# esp32-thing.net
KiCad netlist of a schematic drawn in EAGLE
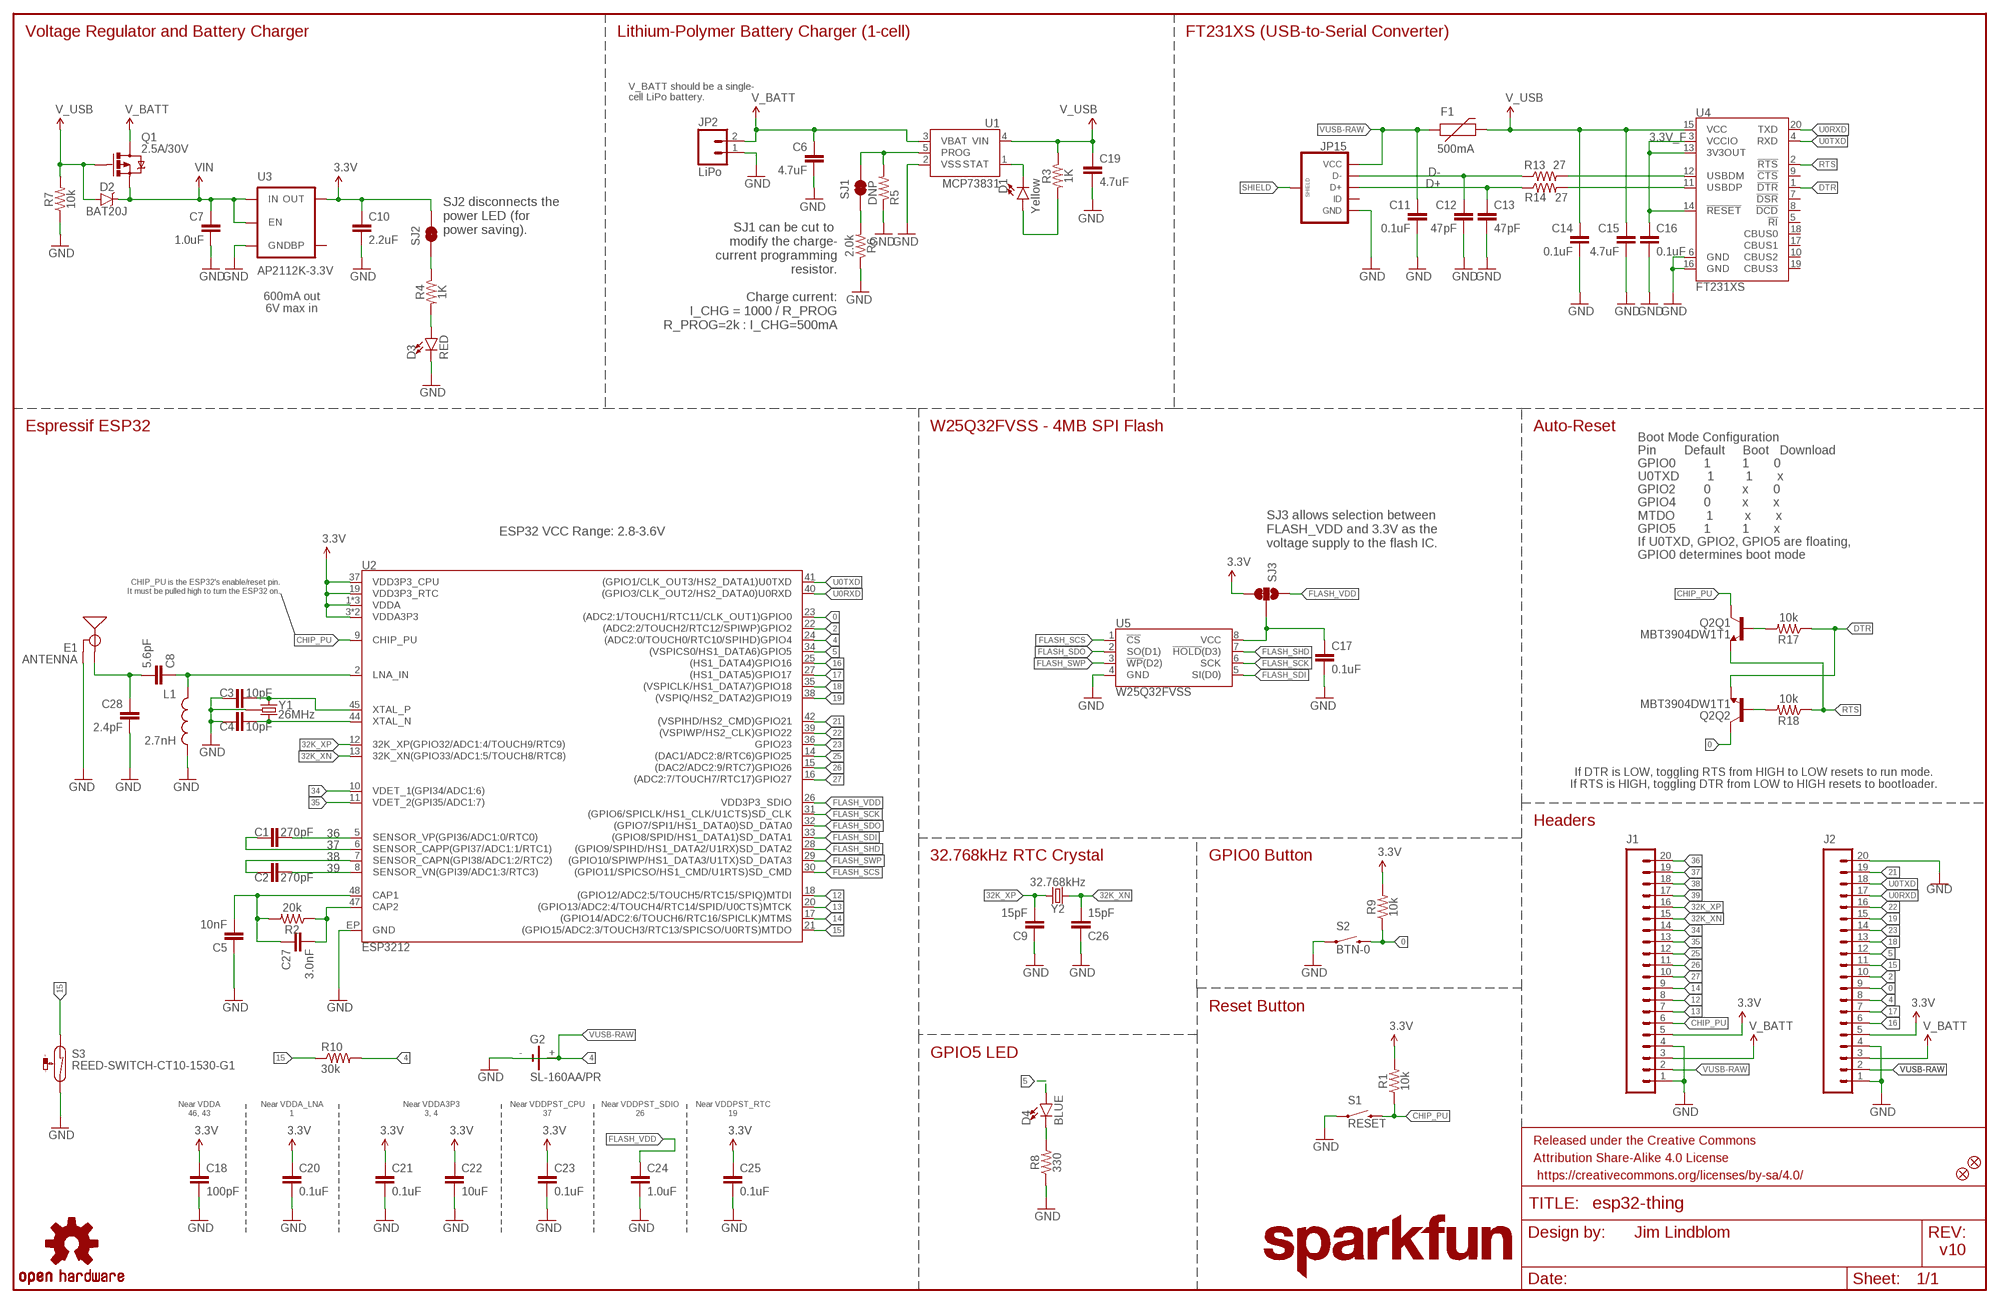
[diagram p0: schematic, sheet 1]

(export (version "E")
  (design (tool "Eeschema 10.0.6"))
  (components
    (comp (ref "C1")
      (value "270pF")
      (footprint "eagle-import:0603")
      (libsource (lib "eagle-import") (part "270PF-50V-5%(0603)"))
    )
    (comp (ref "C2")
      (value "270pF")
      (footprint "eagle-import:0603")
      (libsource (lib "eagle-import") (part "270PF-50V-5%(0603)"))
    )
    (comp (ref "C3")
      (value "10pF")
      (footprint "eagle-import:0603")
      (libsource (lib "eagle-import") (part "10PF-0603-50V-5%"))
    )
    (comp (ref "C4")
      (value "10pF")
      (footprint "eagle-import:0603")
      (libsource (lib "eagle-import") (part "10PF-0603-50V-5%"))
    )
    (comp (ref "C5")
      (value "10nF")
      (footprint "eagle-import:0603")
      (libsource (lib "eagle-import") (part "10NF-0603-50V-10%"))
    )
    (comp (ref "C6")
      (value "4.7uF")
      (footprint "eagle-import:0603")
      (libsource (lib "eagle-import") (part "4.7UF0603"))
    )
    (comp (ref "C7")
      (value "1.0uF")
      (footprint "eagle-import:0805")
      (libsource (lib "eagle-import") (part "1.0UF-0805-25V-(+80/-20%)"))
    )
    (comp (ref "C8")
      (value "5.6pF")
      (footprint "eagle-import:0603")
      (libsource (lib "eagle-import") (part "5.6PF-50V-5%(0603)"))
    )
    (comp (ref "C9")
      (value "15pF")
      (footprint "eagle-import:0603")
      (libsource (lib "eagle-import") (part "15PF-0603-50V-5%"))
    )
    (comp (ref "C10")
      (value "2.2uF")
      (footprint "eagle-import:0603")
      (libsource (lib "eagle-import") (part "2.2UF-0603-10V-20%"))
    )
    (comp (ref "C11")
      (value "0.1uF")
      (footprint "eagle-import:0603")
      (libsource (lib "eagle-import") (part "0.1UF-0603-25V-(+80/-20%)"))
    )
    (comp (ref "C12")
      (value "47pF")
      (footprint "eagle-import:0603")
      (libsource (lib "eagle-import") (part "47PF-0603-50V-5%"))
    )
    (comp (ref "C13")
      (value "47pF")
      (footprint "eagle-import:0603")
      (libsource (lib "eagle-import") (part "47PF-0603-50V-5%"))
    )
    (comp (ref "C14")
      (value "0.1uF")
      (footprint "eagle-import:0603")
      (libsource (lib "eagle-import") (part "0.1UF-0603-25V-(+80/-20%)"))
    )
    (comp (ref "C15")
      (value "4.7uF")
      (footprint "eagle-import:0603-CAP")
      (libsource (lib "eagle-import") (part "4.7UF-6.3V-10%(0603)0603"))
    )
    (comp (ref "C16")
      (value "0.1uF")
      (footprint "eagle-import:0603")
      (libsource (lib "eagle-import") (part "0.1UF-0603-25V-(+80/-20%)"))
    )
    (comp (ref "C17")
      (value "0.1uF")
      (footprint "eagle-import:0603")
      (libsource (lib "eagle-import") (part "0.1UF-0603-25V-(+80/-20%)"))
    )
    (comp (ref "C18")
      (value "100pF")
      (footprint "eagle-import:0603")
      (libsource (lib "eagle-import") (part "100PF-0603-50V-5%"))
    )
    (comp (ref "C19")
      (value "4.7uF")
      (footprint "eagle-import:0603")
      (libsource (lib "eagle-import") (part "4.7UF0603"))
    )
    (comp (ref "C20")
      (value "0.1uF")
      (footprint "eagle-import:0603")
      (libsource (lib "eagle-import") (part "0.1UF-0603-25V-(+80/-20%)"))
    )
    (comp (ref "C21")
      (value "0.1uF")
      (footprint "eagle-import:0603")
      (libsource (lib "eagle-import") (part "0.1UF-0603-25V-(+80/-20%)"))
    )
    (comp (ref "C22")
      (value "10uF")
      (footprint "eagle-import:0603")
      (libsource (lib "eagle-import") (part "10UF-0603-6.3V-20%"))
    )
    (comp (ref "C23")
      (value "0.1uF")
      (footprint "eagle-import:0603")
      (libsource (lib "eagle-import") (part "0.1UF-0603-25V-(+80/-20%)"))
    )
    (comp (ref "C24")
      (value "1.0uF")
      (footprint "eagle-import:0603")
      (libsource (lib "eagle-import") (part "1.0UF-0603-16V-10%"))
    )
    (comp (ref "C25")
      (value "0.1uF")
      (footprint "eagle-import:0603")
      (libsource (lib "eagle-import") (part "0.1UF-0603-25V-(+80/-20%)"))
    )
    (comp (ref "C26")
      (value "15pF")
      (footprint "eagle-import:0603")
      (libsource (lib "eagle-import") (part "15PF-0603-50V-5%"))
    )
    (comp (ref "C27")
      (value "3.0nF")
      (footprint "eagle-import:0603")
      (libsource (lib "eagle-import") (part "3.0NF-0603-50V-5%"))
    )
    (comp (ref "C28")
      (value "2.4pF")
      (footprint "eagle-import:0603")
      (libsource (lib "eagle-import") (part "2.4PF-0603-50V-5%"))
    )
    (comp (ref "D1")
      (value "Yellow")
      (footprint "eagle-import:LED-0603")
      (libsource (lib "eagle-import") (part "LED-YELLOW0603"))
    )
    (comp (ref "D2")
      (value "BAT20J")
      (footprint "eagle-import:SOD-323")
      (libsource (lib "eagle-import") (part "DIODE-SCHOTTKY-BAT20J"))
    )
    (comp (ref "D3")
      (value "RED")
      (footprint "eagle-import:LED-0603")
      (libsource (lib "eagle-import") (part "LED-RED0603"))
    )
    (comp (ref "D4")
      (value "BLUE")
      (footprint "eagle-import:LED-0603")
      (libsource (lib "eagle-import") (part "LED-BLUE0603"))
    )
    (comp (ref "E1")
      (value "ANTENNA")
      (footprint "eagle-import:TRACE_ANTENNA_2.4GHZ_25.7MM_TUNED")
      (libsource (lib "eagle-import") (part "ANTENNATRACE-TUNED"))
    )
    (comp (ref "F1")
      (value "500mA")
      (footprint "eagle-import:PTC-1206")
      (libsource (lib "eagle-import") (part "PTCSMD"))
    )
    (comp (ref "FD1")
      (value "FIDUCIALUFIDUCIAL")
      (footprint "eagle-import:MICRO-FIDUCIAL")
      (libsource (lib "eagle-import") (part "FIDUCIALUFIDUCIAL"))
    )
    (comp (ref "FD2")
      (value "FIDUCIALUFIDUCIAL")
      (footprint "eagle-import:MICRO-FIDUCIAL")
      (libsource (lib "eagle-import") (part "FIDUCIALUFIDUCIAL"))
    )
    (comp (ref "FRAME1")
      (value "FRAME-LEDGER")
      (footprint "eagle-import:CREATIVE_COMMONS")
      (libsource (lib "eagle-import") (part "FRAME-LEDGER"))
    )
    (comp (ref "G2")
      (value "SL-160AA/PR")
      (footprint "eagle-import:SL-160AA_PR")
      (libsource (lib "eagle-import") (part "SL-160AA/PR"))
    )
    (comp (ref "J1")
      (value "M20NOSILK")
      (footprint "eagle-import:1X20_NOSILK")
      (libsource (lib "eagle-import") (part "M20NOSILK"))
    )
    (comp (ref "J2")
      (value "M20NOSILK")
      (footprint "eagle-import:1X20_NOSILK")
      (libsource (lib "eagle-import") (part "M20NOSILK"))
    )
    (comp (ref "JP2")
      (value "LiPo")
      (footprint "eagle-import:JST-2-PTH")
      (libsource (lib "eagle-import") (part "M02JST-PTH-2"))
    )
    (comp (ref "JP15")
      (value "USB_MICROB_PLUGCONN-11752")
      (footprint "eagle-import:USB-B-MICRO-SMD_V03")
      (libsource (lib "eagle-import") (part "USB_MICROB_PLUGCONN-11752"))
    )
    (comp (ref "L1")
      (value "2.7nH")
      (footprint "eagle-import:0603")
      (libsource (lib "eagle-import") (part "INDUCTOR0603"))
    )
    (comp (ref "LOGO1")
      (value "SFE_LOGO_NAME.2_INCH")
      (footprint "eagle-import:SFE_LOGO_NAME_.2")
      (libsource (lib "eagle-import") (part "SFE_LOGO_NAME.2_INCH"))
    )
    (comp (ref "LOGO2")
      (value "OSHW-LOGOMINI")
      (footprint "eagle-import:OSHW-LOGO-MINI")
      (libsource (lib "eagle-import") (part "OSHW-LOGOMINI"))
    )
    (comp (ref "LOGO3")
      (value "SFE_LOGO_NAME.2_INCH")
      (footprint "eagle-import:SFE_LOGO_NAME_.2")
      (libsource (lib "eagle-import") (part "SFE_LOGO_NAME.2_INCH"))
    )
    (comp (ref "Q1")
      (value "2.5A/30V")
      (footprint "eagle-import:SOT23-3")
      (libsource (lib "eagle-import") (part "MOSFET-PCHANNELDMG2307L"))
    )
    (comp (ref "Q2")
      (value "MBT3904DW1T1")
      (footprint "eagle-import:SC70-6")
      (libsource (lib "eagle-import") (part "MBT3904DW1T1"))
    )
    (comp (ref "R1")
      (value "10k")
      (footprint "eagle-import:0603")
      (libsource (lib "eagle-import") (part "10KOHM-1/10W-1%(0603)0603"))
    )
    (comp (ref "R2")
      (value "20k")
      (footprint "eagle-import:0603")
      (libsource (lib "eagle-import") (part "20KOHM-0603-1/10W-1%"))
    )
    (comp (ref "R3")
      (value "1K")
      (footprint "eagle-import:0603")
      (libsource (lib "eagle-import") (part "1KOHM-1/10W-1%(0603)"))
    )
    (comp (ref "R4")
      (value "1K")
      (footprint "eagle-import:0603")
      (libsource (lib "eagle-import") (part "1KOHM-1/10W-1%(0603)"))
    )
    (comp (ref "R5")
      (value "DNP")
      (footprint "eagle-import:1_6W-RES")
      (libsource (lib "eagle-import") (part "RESISTORPTH-1/6W"))
    )
    (comp (ref "R6")
      (value "2.0k")
      (footprint "eagle-import:0603")
      (libsource (lib "eagle-import") (part "2.0KOHM1/10W5%(0603)"))
    )
    (comp (ref "R7")
      (value "10k")
      (footprint "eagle-import:0603")
      (libsource (lib "eagle-import") (part "10KOHM-0603-1/10W-1%"))
    )
    (comp (ref "R8")
      (value "330")
      (footprint "eagle-import:0603")
      (libsource (lib "eagle-import") (part "330OHM1/10W1%(0603)"))
    )
    (comp (ref "R9")
      (value "10k")
      (footprint "eagle-import:0603")
      (libsource (lib "eagle-import") (part "10KOHM-1/10W-1%(0603)0603"))
    )
    (comp (ref "R10")
      (value "30k")
      (footprint "eagle-import:M0805")
      (libsource (lib "eagle-import") (part "R-US_M0805"))
    )
    (comp (ref "R13")
      (value "27")
      (footprint "eagle-import:0603")
      (libsource (lib "eagle-import") (part "27OHM1/10W1%(0603)0603-RES"))
    )
    (comp (ref "R14")
      (value "27")
      (footprint "eagle-import:0603")
      (libsource (lib "eagle-import") (part "27OHM1/10W1%(0603)0603-RES"))
    )
    (comp (ref "R17")
      (value "10k")
      (footprint "eagle-import:0603")
      (libsource (lib "eagle-import") (part "10KOHM-0603-1/10W-1%"))
    )
    (comp (ref "R18")
      (value "10k")
      (footprint "eagle-import:0603")
      (libsource (lib "eagle-import") (part "10KOHM-0603-1/10W-1%"))
    )
    (comp (ref "S1")
      (value "RESET")
      (footprint "eagle-import:TACTILE_SWITCH_SMD_4.6X2.8MM")
      (libsource (lib "eagle-import") (part "SWITCH-MOMENTARY-2SMD-4.6X2.8MM"))
    )
    (comp (ref "S2")
      (value "BTN-0")
      (footprint "eagle-import:TACTILE_SWITCH_SMD_4.6X2.8MM")
      (libsource (lib "eagle-import") (part "SWITCH-MOMENTARY-2SMD-4.6X2.8MM"))
    )
    (comp (ref "S3")
      (value "REED-SWITCH-CT10-1530-G1")
      (footprint "eagle-import:CT10-G1")
      (fields (field (name "MF") "COTO TECHNOLOGY") (field (name "MPN") "CT10-1530-G1"))
      (libsource (lib "eagle-import") (part "REED-SWITCH-CT10-1530-G1"))
    )
    (comp (ref "SJ1")
      (value "JUMPER-PAD-2-NC_BY_TRACE")
      (footprint "eagle-import:PAD-JUMPER-2-NC_BY_TRACE_YES_SILK")
      (libsource (lib "eagle-import") (part "JUMPER-PAD-2-NC_BY_TRACE"))
    )
    (comp (ref "SJ2")
      (value "JUMPER-PAD-2-NC_BY_TRACE")
      (footprint "eagle-import:PAD-JUMPER-2-NC_BY_TRACE_YES_SILK")
      (libsource (lib "eagle-import") (part "JUMPER-PAD-2-NC_BY_TRACE"))
    )
    (comp (ref "SJ3")
      (value "JUMPER-PAD-3-2OF3_NC_BY_TRACE_SMALL")
      (footprint "eagle-import:PAD-JUMPER-3-2OF3_NC_BY_TRACE_YES_SILK_FULL_BOX")
      (libsource (lib "eagle-import") (part "JUMPER-PAD-3-2OF3_NC_BY_TRACE_SMALL"))
    )
    (comp (ref "U1")
      (value "MCP73831")
      (footprint "eagle-import:SOT23-5")
      (libsource (lib "eagle-import") (part "MCP73831"))
    )
    (comp (ref "U2")
      (value "ESP3212")
      (footprint "eagle-import:QFN48-0.4MM")
      (libsource (lib "eagle-import") (part "ESP3212"))
    )
    (comp (ref "U3")
      (value "AP2112K-3.3V")
      (footprint "eagle-import:SOT23-5")
      (libsource (lib "eagle-import") (part "V_REG_LDOSMD"))
    )
    (comp (ref "U4")
      (value "FT231XS")
      (footprint "eagle-import:SSOP20_L")
      (libsource (lib "eagle-import") (part "FT231XS"))
    )
    (comp (ref "U5")
      (value "W25Q32FVSS")
      (footprint "eagle-import:SOIC-8")
      (libsource (lib "eagle-import") (part "W25Q32FVSS"))
    )
    (comp (ref "Y1")
      (value "26MHz")
      (footprint "eagle-import:CRYSTAL-SMD-3.2X2.5")
      (libsource (lib "eagle-import") (part "CRYSTAL-GROUNDED3.2X2.5"))
    )
    (comp (ref "Y2")
      (value "32.768kHz")
      (footprint "eagle-import:CRYSTAL-SMD-3.2X1.5MM")
      (libsource (lib "eagle-import") (part "CRYSTAL-32.768KHZSMD-3.2X1.5"))
    )
  )
  (nets
    (net (code "1") (name "/3.3V_F") (class "Default")
      (node (ref "C16") (pin "1") (pinfunction "1_1") (pintype "passive"))
      (node (ref "U4") (pin "13") (pinfunction "3V3OUT_13") (pintype "bidirectional"))
      (node (ref "U4") (pin "14") (pinfunction "~{RESET}_14") (pintype "bidirectional"))
      (node (ref "U4") (pin "3") (pinfunction "VCCIO_3") (pintype "bidirectional"))
    )
    (net (code "2") (name "/D+") (class "Default")
      (node (ref "C13") (pin "1") (pinfunction "1_1") (pintype "passive"))
      (node (ref "JP15") (pin "D+") (pinfunction "D+_D+") (pintype "bidirectional"))
      (node (ref "R14") (pin "1") (pinfunction "1_1") (pintype "passive"))
    )
    (net (code "3") (name "/D-") (class "Default")
      (node (ref "C12") (pin "1") (pinfunction "1_1") (pintype "passive"))
      (node (ref "JP15") (pin "D-") (pinfunction "D-_D-") (pintype "bidirectional"))
      (node (ref "R13") (pin "1") (pinfunction "1_1") (pintype "passive"))
    )
    (net (code "4") (name "0") (class "Default")
      (node (ref "J2") (pin "9") (pinfunction "9_9") (pintype "passive"))
      (node (ref "Q2") (pin "6") (pinfunction "C_6") (pintype "passive"))
      (node (ref "R9") (pin "1") (pinfunction "1_1") (pintype "passive"))
      (node (ref "S2") (pin "3") (pinfunction "2_3") (pintype "passive"))
      (node (ref "S2") (pin "4") (pinfunction "2_4") (pintype "passive"))
      (node (ref "U2") (pin "23") (pinfunction "(ADC2:1/TOUCH1/RTC11/CLK_OUT1)GPIO0_23") (pintype "bidirectional"))
    )
    (net (code "5") (name "2") (class "Default")
      (node (ref "J2") (pin "10") (pinfunction "10_10") (pintype "passive"))
      (node (ref "U2") (pin "22") (pinfunction "(ADC2:2/TOUCH2/RTC12/SPIWP)GPIO2_22") (pintype "bidirectional"))
    )
    (net (code "6") (name "3.3V") (class "Default")
      (node (ref "C10") (pin "1") (pinfunction "1_1") (pintype "passive"))
      (node (ref "C18") (pin "1") (pinfunction "1_1") (pintype "passive"))
      (node (ref "C20") (pin "1") (pinfunction "1_1") (pintype "passive"))
      (node (ref "C21") (pin "1") (pinfunction "1_1") (pintype "passive"))
      (node (ref "C22") (pin "1") (pinfunction "1_1") (pintype "passive"))
      (node (ref "C23") (pin "1") (pinfunction "1_1") (pintype "passive"))
      (node (ref "C25") (pin "1") (pinfunction "1_1") (pintype "passive"))
      (node (ref "J1") (pin "5") (pinfunction "5_5") (pintype "passive"))
      (node (ref "J2") (pin "5") (pinfunction "5_5") (pintype "passive"))
      (node (ref "R1") (pin "2") (pinfunction "2_2") (pintype "passive"))
      (node (ref "R9") (pin "2") (pinfunction "2_2") (pintype "passive"))
      (node (ref "SJ2") (pin "2") (pinfunction "2_2") (pintype "passive"))
      (node (ref "SJ3") (pin "3") (pinfunction "3_3") (pintype "passive"))
      (node (ref "U2") (pin "1") (pinfunction "VDDA_1") (pintype "bidirectional"))
      (node (ref "U2") (pin "19") (pinfunction "VDD3P3_RTC_19") (pintype "bidirectional"))
      (node (ref "U2") (pin "3") (pinfunction "VDDA3P3_3") (pintype "bidirectional"))
      (node (ref "U2") (pin "37") (pinfunction "VDD3P3_CPU_37") (pintype "bidirectional"))
      (node (ref "U2") (pin "4") (pinfunction "VDDA3P3_4") (pintype "bidirectional"))
      (node (ref "U2") (pin "43") (pinfunction "VDDA_43") (pintype "bidirectional"))
      (node (ref "U2") (pin "46") (pinfunction "VDDA_46") (pintype "bidirectional"))
      (node (ref "U3") (pin "5") (pinfunction "OUT_5") (pintype "passive"))
    )
    (net (code "7") (name "4") (class "Default")
      (node (ref "J2") (pin "8") (pinfunction "8_8") (pintype "passive"))
      (node (ref "U2") (pin "24") (pinfunction "(ADC2:0/TOUCH0/RTC10/SPIHD)GPIO4_24") (pintype "bidirectional"))
    )
    (net (code "8") (name "5") (class "Default")
      (node (ref "D4") (pin "A") (pinfunction "A_A") (pintype "passive"))
      (node (ref "J2") (pin "12") (pinfunction "12_12") (pintype "passive"))
      (node (ref "U2") (pin "34") (pinfunction "(VSPICS0/HS1_DATA6)GPIO5_34") (pintype "bidirectional"))
    )
    (net (code "9") (name "12") (class "Default")
      (node (ref "J1") (pin "8") (pinfunction "8_8") (pintype "passive"))
      (node (ref "U2") (pin "18") (pinfunction "(GPIO12/ADC2:5/TOUCH5/RTC15/SPIQ)MTDI_18") (pintype "bidirectional"))
    )
    (net (code "10") (name "13") (class "Default")
      (node (ref "J1") (pin "7") (pinfunction "7_7") (pintype "passive"))
      (node (ref "U2") (pin "20") (pinfunction "(GPIO13/ADC2:4/TOUCH4/RTC14/SPID/U0CTS)MTCK_20") (pintype "bidirectional"))
    )
    (net (code "11") (name "14") (class "Default")
      (node (ref "J1") (pin "9") (pinfunction "9_9") (pintype "passive"))
      (node (ref "U2") (pin "17") (pinfunction "(GPIO14/ADC2:6/TOUCH6/RTC16/SPICLK)MTMS_17") (pintype "bidirectional"))
    )
    (net (code "12") (name "15") (class "Default")
      (node (ref "J2") (pin "11") (pinfunction "11_11") (pintype "passive"))
      (node (ref "U2") (pin "21") (pinfunction "(GPIO15/ADC2:3/TOUCH3/RTC13/SPICSO/U0RTS)MTDO_21") (pintype "bidirectional"))
    )
    (net (code "13") (name "16") (class "Default")
      (node (ref "J2") (pin "6") (pinfunction "6_6") (pintype "passive"))
      (node (ref "U2") (pin "25") (pinfunction "(HS1_DATA4)GPIO16_25") (pintype "bidirectional"))
    )
    (net (code "14") (name "17") (class "Default")
      (node (ref "J2") (pin "7") (pinfunction "7_7") (pintype "passive"))
      (node (ref "U2") (pin "27") (pinfunction "(HS1_DATA5)GPIO17_27") (pintype "bidirectional"))
    )
    (net (code "15") (name "18") (class "Default")
      (node (ref "J2") (pin "13") (pinfunction "13_13") (pintype "passive"))
      (node (ref "U2") (pin "35") (pinfunction "(VSPICLK/HS1_DATA7)GPIO18_35") (pintype "bidirectional"))
    )
    (net (code "16") (name "19") (class "Default")
      (node (ref "J2") (pin "15") (pinfunction "15_15") (pintype "passive"))
      (node (ref "U2") (pin "38") (pinfunction "(VSPIQ/HS2_DATA2)GPIO19_38") (pintype "bidirectional"))
    )
    (net (code "17") (name "21") (class "Default")
      (node (ref "J2") (pin "19") (pinfunction "19_19") (pintype "passive"))
      (node (ref "U2") (pin "42") (pinfunction "(VSPIHD/HS2_CMD)GPIO21_42") (pintype "bidirectional"))
    )
    (net (code "18") (name "22") (class "Default")
      (node (ref "J2") (pin "16") (pinfunction "16_16") (pintype "passive"))
      (node (ref "U2") (pin "39") (pinfunction "(VSPIWP/HS2_CLK)GPIO22_39") (pintype "bidirectional"))
    )
    (net (code "19") (name "23") (class "Default")
      (node (ref "J2") (pin "14") (pinfunction "14_14") (pintype "passive"))
      (node (ref "U2") (pin "36") (pinfunction "GPIO23_36") (pintype "bidirectional"))
    )
    (net (code "20") (name "25") (class "Default")
      (node (ref "J1") (pin "12") (pinfunction "12_12") (pintype "passive"))
      (node (ref "U2") (pin "14") (pinfunction "(DAC1/ADC2:8/RTC6)GPIO25_14") (pintype "bidirectional"))
    )
    (net (code "21") (name "26") (class "Default")
      (node (ref "J1") (pin "11") (pinfunction "11_11") (pintype "passive"))
      (node (ref "U2") (pin "15") (pinfunction "(DAC2/ADC2:9/RTC7)GPIO26_15") (pintype "bidirectional"))
    )
    (net (code "22") (name "27") (class "Default")
      (node (ref "J1") (pin "10") (pinfunction "10_10") (pintype "passive"))
      (node (ref "U2") (pin "16") (pinfunction "(ADC2:7/TOUCH7/RTC17)GPIO27_16") (pintype "bidirectional"))
    )
    (net (code "23") (name "32K_XN") (class "Default")
      (node (ref "C26") (pin "2") (pinfunction "2_2") (pintype "passive"))
      (node (ref "J1") (pin "15") (pinfunction "15_15") (pintype "passive"))
      (node (ref "U2") (pin "13") (pinfunction "32K_XN(GPIO33/ADC1:5/TOUCH8/RTC8)_13") (pintype "bidirectional"))
      (node (ref "Y2") (pin "P$2") (pinfunction "2_P$2") (pintype "passive"))
    )
    (net (code "24") (name "32K_XP") (class "Default")
      (node (ref "C9") (pin "2") (pinfunction "2_2") (pintype "passive"))
      (node (ref "J1") (pin "16") (pinfunction "16_16") (pintype "passive"))
      (node (ref "U2") (pin "12") (pinfunction "32K_XP(GPIO32/ADC1:4/TOUCH9/RTC9)_12") (pintype "bidirectional"))
      (node (ref "Y2") (pin "P$1") (pinfunction "1_P$1") (pintype "passive"))
    )
    (net (code "25") (name "34") (class "Default")
      (node (ref "J1") (pin "14") (pinfunction "14_14") (pintype "passive"))
      (node (ref "U2") (pin "10") (pinfunction "VDET_1(GPI34/ADC1:6)_10") (pintype "bidirectional"))
    )
    (net (code "26") (name "35") (class "Default")
      (node (ref "J1") (pin "13") (pinfunction "13_13") (pintype "passive"))
      (node (ref "U2") (pin "11") (pinfunction "VDET_2(GPI35/ADC1:7)_11") (pintype "bidirectional"))
    )
    (net (code "27") (name "36") (class "Default")
      (node (ref "C1") (pin "2") (pinfunction "2_2") (pintype "passive"))
      (node (ref "J1") (pin "20") (pinfunction "20_20") (pintype "passive"))
      (node (ref "U2") (pin "5") (pinfunction "SENSOR_VP(GPI36/ADC1:0/RTC0)_5") (pintype "bidirectional"))
    )
    (net (code "28") (name "37") (class "Default")
      (node (ref "C1") (pin "1") (pinfunction "1_1") (pintype "passive"))
      (node (ref "J1") (pin "19") (pinfunction "19_19") (pintype "passive"))
      (node (ref "U2") (pin "6") (pinfunction "SENSOR_CAPP(GPI37/ADC1:1/RTC1)_6") (pintype "bidirectional"))
    )
    (net (code "29") (name "38") (class "Default")
      (node (ref "C2") (pin "1") (pinfunction "1_1") (pintype "passive"))
      (node (ref "J1") (pin "18") (pinfunction "18_18") (pintype "passive"))
      (node (ref "U2") (pin "7") (pinfunction "SENSOR_CAPN(GPI38/ADC1:2/RTC2)_7") (pintype "bidirectional"))
    )
    (net (code "30") (name "39") (class "Default")
      (node (ref "C2") (pin "2") (pinfunction "2_2") (pintype "passive"))
      (node (ref "J1") (pin "17") (pinfunction "17_17") (pintype "passive"))
      (node (ref "U2") (pin "8") (pinfunction "SENSOR_VN(GPI39/ADC1:3/RTC3)_8") (pintype "bidirectional"))
    )
    (net (code "31") (name "CHIP_PU") (class "Default")
      (node (ref "J1") (pin "6") (pinfunction "6_6") (pintype "passive"))
      (node (ref "Q2") (pin "3") (pinfunction "C_3") (pintype "passive"))
      (node (ref "R1") (pin "1") (pinfunction "1_1") (pintype "passive"))
      (node (ref "S1") (pin "3") (pinfunction "2_3") (pintype "passive"))
      (node (ref "S1") (pin "4") (pinfunction "2_4") (pintype "passive"))
      (node (ref "U2") (pin "9") (pinfunction "CHIP_PU_9") (pintype "bidirectional"))
    )
    (net (code "32") (name "DTR") (class "Default")
      (node (ref "Q2") (pin "1") (pinfunction "E_1") (pintype "passive"))
      (node (ref "R17") (pin "1") (pinfunction "1_1") (pintype "passive"))
      (node (ref "U4") (pin "1") (pinfunction "~{DTR}_1") (pintype "bidirectional"))
    )
    (net (code "33") (name "FLASH_SCK") (class "Default")
      (node (ref "U2") (pin "31") (pinfunction "(GPIO6/SPICLK/HS1_CLK/U1CTS)SD_CLK_31") (pintype "bidirectional"))
      (node (ref "U5") (pin "6") (pinfunction "SCK_6") (pintype "bidirectional"))
    )
    (net (code "34") (name "FLASH_SCS") (class "Default")
      (node (ref "U2") (pin "30") (pinfunction "(GPIO11/SPICSO/HS1_CMD/U1RTS)SD_CMD_30") (pintype "bidirectional"))
      (node (ref "U5") (pin "1") (pinfunction "~{CS}_1") (pintype "bidirectional"))
    )
    (net (code "35") (name "FLASH_SDI") (class "Default")
      (node (ref "U2") (pin "33") (pinfunction "(GPIO8/SPID/HS1_DATA1)SD_DATA1_33") (pintype "bidirectional"))
      (node (ref "U5") (pin "5") (pinfunction "SI(D0)_5") (pintype "bidirectional"))
    )
    (net (code "36") (name "FLASH_SDO") (class "Default")
      (node (ref "U2") (pin "32") (pinfunction "(GPIO7/SPI1/HS1_DATA0)SD_DATA0_32") (pintype "bidirectional"))
      (node (ref "U5") (pin "2") (pinfunction "SO(D1)_2") (pintype "bidirectional"))
    )
    (net (code "37") (name "FLASH_SHD") (class "Default")
      (node (ref "U2") (pin "28") (pinfunction "(GPIO9/SPIHD/HS1_DATA2/U1RX)SD_DATA2_28") (pintype "bidirectional"))
      (node (ref "U5") (pin "7") (pinfunction "~{HOLD}(D3)_7") (pintype "bidirectional"))
    )
    (net (code "38") (name "FLASH_SWP") (class "Default")
      (node (ref "U2") (pin "29") (pinfunction "(GPIO10/SPIWP/HS1_DATA3/U1TX)SD_DATA3_29") (pintype "bidirectional"))
      (node (ref "U5") (pin "3") (pinfunction "~{WP}(D2)_3") (pintype "bidirectional"))
    )
    (net (code "39") (name "FLASH_VDD") (class "Default")
      (node (ref "C24") (pin "1") (pinfunction "1_1") (pintype "passive"))
      (node (ref "SJ3") (pin "1") (pinfunction "1_1") (pintype "passive"))
      (node (ref "U2") (pin "26") (pinfunction "VDD3P3_SDIO_26") (pintype "bidirectional"))
    )
    (net (code "40") (name "GND") (class "Default")
      (node (ref "C10") (pin "2") (pinfunction "2_2") (pintype "passive"))
      (node (ref "C11") (pin "2") (pinfunction "2_2") (pintype "passive"))
      (node (ref "C12") (pin "2") (pinfunction "2_2") (pintype "passive"))
      (node (ref "C13") (pin "2") (pinfunction "2_2") (pintype "passive"))
      (node (ref "C14") (pin "2") (pinfunction "2_2") (pintype "passive"))
      (node (ref "C15") (pin "2") (pinfunction "2_2") (pintype "passive"))
      (node (ref "C16") (pin "2") (pinfunction "2_2") (pintype "passive"))
      (node (ref "C17") (pin "2") (pinfunction "2_2") (pintype "passive"))
      (node (ref "C18") (pin "2") (pinfunction "2_2") (pintype "passive"))
      (node (ref "C19") (pin "2") (pinfunction "2_2") (pintype "passive"))
      (node (ref "C20") (pin "2") (pinfunction "2_2") (pintype "passive"))
      (node (ref "C21") (pin "2") (pinfunction "2_2") (pintype "passive"))
      (node (ref "C22") (pin "2") (pinfunction "2_2") (pintype "passive"))
      (node (ref "C23") (pin "2") (pinfunction "2_2") (pintype "passive"))
      (node (ref "C24") (pin "2") (pinfunction "2_2") (pintype "passive"))
      (node (ref "C25") (pin "2") (pinfunction "2_2") (pintype "passive"))
      (node (ref "C26") (pin "1") (pinfunction "1_1") (pintype "passive"))
      (node (ref "C28") (pin "2") (pinfunction "2_2") (pintype "passive"))
      (node (ref "C3") (pin "1") (pinfunction "1_1") (pintype "passive"))
      (node (ref "C4") (pin "1") (pinfunction "1_1") (pintype "passive"))
      (node (ref "C5") (pin "1") (pinfunction "1_1") (pintype "passive"))
      (node (ref "C6") (pin "2") (pinfunction "2_2") (pintype "passive"))
      (node (ref "C7") (pin "2") (pinfunction "2_2") (pintype "passive"))
      (node (ref "C9") (pin "1") (pinfunction "1_1") (pintype "passive"))
      (node (ref "D3") (pin "C") (pinfunction "C_C") (pintype "passive"))
      (node (ref "E1") (pin "GND") (pinfunction "GND_GND") (pintype "bidirectional"))
      (node (ref "E1") (pin "GND2") (pinfunction "GND_GND2") (pintype "bidirectional"))
      (node (ref "G2") (pin "+") (pinfunction "+_+") (pintype "passive"))
      (node (ref "G2") (pin "-") (pinfunction "-_-") (pintype "passive"))
      (node (ref "J1") (pin "1") (pinfunction "1_1") (pintype "passive"))
      (node (ref "J1") (pin "4") (pinfunction "4_4") (pintype "passive"))
      (node (ref "J2") (pin "1") (pinfunction "1_1") (pintype "passive"))
      (node (ref "J2") (pin "20") (pinfunction "20_20") (pintype "passive"))
      (node (ref "J2") (pin "4") (pinfunction "4_4") (pintype "passive"))
      (node (ref "JP15") (pin "GND") (pinfunction "GND_GND") (pintype "bidirectional"))
      (node (ref "JP2") (pin "1") (pinfunction "1_1") (pintype "passive"))
      (node (ref "L1") (pin "2") (pinfunction "2_2") (pintype "passive"))
      (node (ref "R5") (pin "1") (pinfunction "1_1") (pintype "passive"))
      (node (ref "R6") (pin "1") (pinfunction "1_1") (pintype "passive"))
      (node (ref "R7") (pin "1") (pinfunction "1_1") (pintype "passive"))
      (node (ref "R8") (pin "1") (pinfunction "1_1") (pintype "passive"))
      (node (ref "S1") (pin "1") (pinfunction "1_1") (pintype "passive"))
      (node (ref "S1") (pin "2") (pinfunction "1_2") (pintype "passive"))
      (node (ref "S2") (pin "1") (pinfunction "1_1") (pintype "passive"))
      (node (ref "S2") (pin "2") (pinfunction "1_2") (pintype "passive"))
      (node (ref "S3") (pin "2") (pinfunction "2_2") (pintype "passive"))
      (node (ref "U1") (pin "2") (pinfunction "VSS_2") (pintype "power_in"))
      (node (ref "U2") (pin "EP") (pinfunction "GND_EP") (pintype "bidirectional"))
      (node (ref "U3") (pin "2") (pinfunction "GND_2") (pintype "input"))
      (node (ref "U4") (pin "16") (pinfunction "GND_16") (pintype "bidirectional"))
      (node (ref "U4") (pin "6") (pinfunction "GND_6") (pintype "bidirectional"))
      (node (ref "U5") (pin "4") (pinfunction "GND_4") (pintype "bidirectional"))
      (node (ref "Y1") (pin "2") (pinfunction "GND_2") (pintype "passive"))
      (node (ref "Y1") (pin "4") (pinfunction "GND_4") (pintype "passive"))
    )
    (net (code "41") (name "Net-(D1-PadA)") (class "Default")
      (node (ref "D1") (pin "A") (pinfunction "A_A") (pintype "passive"))
      (node (ref "R3") (pin "2") (pinfunction "2_2") (pintype "passive"))
    )
    (net (code "42") (name "Net-(D3-PadA)") (class "Default")
      (node (ref "D3") (pin "A") (pinfunction "A_A") (pintype "passive"))
      (node (ref "R4") (pin "2") (pinfunction "2_2") (pintype "passive"))
    )
    (net (code "43") (name "Net-(D4-PadC)") (class "Default")
      (node (ref "D4") (pin "C") (pinfunction "C_C") (pintype "passive"))
      (node (ref "R8") (pin "2") (pinfunction "2_2") (pintype "passive"))
    )
    (net (code "44") (name "Net-(E1-SIGNAL)") (class "Default")
      (node (ref "C28") (pin "1") (pinfunction "1_1") (pintype "passive"))
      (node (ref "C8") (pin "2") (pinfunction "2_2") (pintype "passive"))
      (node (ref "E1") (pin "ANT") (pinfunction "SIGNAL_ANT") (pintype "bidirectional"))
    )
    (net (code "45") (name "Net-(Q2A-B)") (class "Default")
      (node (ref "Q2") (pin "5") (pinfunction "B_5") (pintype "passive"))
      (node (ref "R17") (pin "2") (pinfunction "2_2") (pintype "passive"))
    )
    (net (code "46") (name "Net-(Q2B-B)") (class "Default")
      (node (ref "Q2") (pin "2") (pinfunction "B_2") (pintype "passive"))
      (node (ref "R18") (pin "2") (pinfunction "2_2") (pintype "passive"))
    )
    (net (code "47") (name "Net-(R4-Pad1)") (class "Default")
      (node (ref "R4") (pin "1") (pinfunction "1_1") (pintype "passive"))
      (node (ref "SJ2") (pin "1") (pinfunction "1_1") (pintype "passive"))
    )
    (net (code "48") (name "Net-(R6-Pad2)") (class "Default")
      (node (ref "R6") (pin "2") (pinfunction "2_2") (pintype "passive"))
      (node (ref "SJ1") (pin "1") (pinfunction "1_1") (pintype "passive"))
    )
    (net (code "49") (name "Net-(U1-PROG)") (class "Default")
      (node (ref "R5") (pin "2") (pinfunction "2_2") (pintype "passive"))
      (node (ref "SJ1") (pin "2") (pinfunction "2_2") (pintype "passive"))
      (node (ref "U1") (pin "5") (pinfunction "PROG_5") (pintype "input"))
    )
    (net (code "50") (name "Net-(U1-STAT)") (class "Default")
      (node (ref "D1") (pin "C") (pinfunction "C_C") (pintype "passive"))
      (node (ref "U1") (pin "1") (pinfunction "STAT_1") (pintype "output"))
    )
    (net (code "51") (name "Net-(U2-CAP1)") (class "Default")
      (node (ref "C27") (pin "1") (pinfunction "1_1") (pintype "passive"))
      (node (ref "C5") (pin "2") (pinfunction "2_2") (pintype "passive"))
      (node (ref "R2") (pin "2") (pinfunction "2_2") (pintype "passive"))
      (node (ref "U2") (pin "48") (pinfunction "CAP1_48") (pintype "bidirectional"))
    )
    (net (code "52") (name "Net-(U2-CAP2)") (class "Default")
      (node (ref "C27") (pin "2") (pinfunction "2_2") (pintype "passive"))
      (node (ref "R2") (pin "1") (pinfunction "1_1") (pintype "passive"))
      (node (ref "U2") (pin "47") (pinfunction "CAP2_47") (pintype "bidirectional"))
    )
    (net (code "53") (name "Net-(U2-LNA_IN)") (class "Default")
      (node (ref "C8") (pin "1") (pinfunction "1_1") (pintype "passive"))
      (node (ref "L1") (pin "1") (pinfunction "1_1") (pintype "passive"))
      (node (ref "U2") (pin "2") (pinfunction "LNA_IN_2") (pintype "bidirectional"))
    )
    (net (code "54") (name "Net-(U2-XTAL_N)") (class "Default")
      (node (ref "C4") (pin "2") (pinfunction "2_2") (pintype "passive"))
      (node (ref "U2") (pin "44") (pinfunction "XTAL_N_44") (pintype "bidirectional"))
      (node (ref "Y1") (pin "3") (pinfunction "2_3") (pintype "passive"))
    )
    (net (code "55") (name "Net-(U2-XTAL_P)") (class "Default")
      (node (ref "C3") (pin "2") (pinfunction "2_2") (pintype "passive"))
      (node (ref "U2") (pin "45") (pinfunction "XTAL_P_45") (pintype "bidirectional"))
      (node (ref "Y1") (pin "1") (pinfunction "1_1") (pintype "passive"))
    )
    (net (code "56") (name "Net-(U4-USBDM)") (class "Default")
      (node (ref "R13") (pin "2") (pinfunction "2_2") (pintype "passive"))
      (node (ref "U4") (pin "12") (pinfunction "USBDM_12") (pintype "bidirectional"))
    )
    (net (code "57") (name "Net-(U4-USBDP)") (class "Default")
      (node (ref "R14") (pin "2") (pinfunction "2_2") (pintype "passive"))
      (node (ref "U4") (pin "11") (pinfunction "USBDP_11") (pintype "bidirectional"))
    )
    (net (code "58") (name "Net-(U5-VCC)") (class "Default")
      (node (ref "C17") (pin "1") (pinfunction "1_1") (pintype "passive"))
      (node (ref "SJ3") (pin "2") (pinfunction "2_2") (pintype "passive"))
      (node (ref "U5") (pin "8") (pinfunction "VCC_8") (pintype "bidirectional"))
    )
    (net (code "59") (name "RTS") (class "Default")
      (node (ref "Q2") (pin "4") (pinfunction "E_4") (pintype "passive"))
      (node (ref "R18") (pin "1") (pinfunction "1_1") (pintype "passive"))
      (node (ref "U4") (pin "2") (pinfunction "~{RTS}_2") (pintype "bidirectional"))
    )
    (net (code "60") (name "SHIELD") (class "Default")
      (node (ref "JP15") (pin "SHIELD1") (pinfunction "SHIELD_SHIELD1") (pintype "bidirectional"))
      (node (ref "JP15") (pin "SHIELD2") (pinfunction "SHIELD_SHIELD2") (pintype "bidirectional"))
      (node (ref "JP15") (pin "SHIELD3") (pinfunction "SHIELD_SHIELD3") (pintype "bidirectional"))
    )
    (net (code "61") (name "U0RXD") (class "Default")
      (node (ref "J2") (pin "17") (pinfunction "17_17") (pintype "passive"))
      (node (ref "U2") (pin "40") (pinfunction "(GPIO3/CLK_OUT2/HS2_DATA0)U0RXD_40") (pintype "bidirectional"))
      (node (ref "U4") (pin "20") (pinfunction "TXD_20") (pintype "bidirectional"))
    )
    (net (code "62") (name "U0TXD") (class "Default")
      (node (ref "J2") (pin "18") (pinfunction "18_18") (pintype "passive"))
      (node (ref "U2") (pin "41") (pinfunction "(GPIO1/CLK_OUT3/HS2_DATA1)U0TXD_41") (pintype "bidirectional"))
      (node (ref "U4") (pin "4") (pinfunction "RXD_4") (pintype "bidirectional"))
    )
    (net (code "63") (name "VIN") (class "Default")
      (node (ref "C7") (pin "1") (pinfunction "1_1") (pintype "passive"))
      (node (ref "D2") (pin "C") (pinfunction "C_C") (pintype "passive"))
      (node (ref "Q1") (pin "2") (pinfunction "S_2") (pintype "passive"))
      (node (ref "U3") (pin "1") (pinfunction "IN_1") (pintype "input"))
      (node (ref "U3") (pin "3") (pinfunction "EN_3") (pintype "input"))
    )
    (net (code "64") (name "VUSB-RAW") (class "Default")
      (node (ref "C11") (pin "1") (pinfunction "1_1") (pintype "passive"))
      (node (ref "F1") (pin "1") (pinfunction "1_1") (pintype "bidirectional"))
      (node (ref "J1") (pin "2") (pinfunction "2_2") (pintype "passive"))
      (node (ref "J2") (pin "2") (pinfunction "2_2") (pintype "passive"))
      (node (ref "JP15") (pin "VBUS") (pinfunction "VCC_VBUS") (pintype "bidirectional"))
    )
    (net (code "65") (name "V_BATT") (class "Default")
      (node (ref "C6") (pin "1") (pinfunction "1_1") (pintype "passive"))
      (node (ref "J1") (pin "3") (pinfunction "3_3") (pintype "passive"))
      (node (ref "J2") (pin "3") (pinfunction "3_3") (pintype "passive"))
      (node (ref "JP2") (pin "2") (pinfunction "2_2") (pintype "passive"))
      (node (ref "Q1") (pin "3") (pinfunction "D_3") (pintype "passive"))
      (node (ref "U1") (pin "3") (pinfunction "VBAT_3") (pintype "power_in"))
    )
    (net (code "66") (name "V_USB") (class "Default")
      (node (ref "C14") (pin "1") (pinfunction "1_1") (pintype "passive"))
      (node (ref "C15") (pin "1") (pinfunction "1_1") (pintype "passive"))
      (node (ref "C19") (pin "1") (pinfunction "1_1") (pintype "passive"))
      (node (ref "D2") (pin "A") (pinfunction "A_A") (pintype "passive"))
      (node (ref "F1") (pin "2") (pinfunction "2_2") (pintype "bidirectional"))
      (node (ref "Q1") (pin "1") (pinfunction "G_1") (pintype "passive"))
      (node (ref "R3") (pin "1") (pinfunction "1_1") (pintype "passive"))
      (node (ref "R7") (pin "2") (pinfunction "2_2") (pintype "passive"))
      (node (ref "U1") (pin "4") (pinfunction "VIN_4") (pintype "power_in"))
      (node (ref "U4") (pin "15") (pinfunction "VCC_15") (pintype "bidirectional"))
    )
    (net (code "67") (name "unconnected-(JP15-PadID)") (class "Default")
      (node (ref "JP15") (pin "ID") (pinfunction "ID_ID") (pintype "bidirectional"))
    )
    (net (code "68") (name "unconnected-(R10-Pad1)") (class "Default")
      (node (ref "R10") (pin "1") (pinfunction "1_1") (pintype "passive"))
    )
    (net (code "69") (name "unconnected-(R10-Pad2)") (class "Default")
      (node (ref "R10") (pin "2") (pinfunction "2_2") (pintype "passive"))
    )
    (net (code "70") (name "unconnected-(S3-Pad1)") (class "Default")
      (node (ref "S3") (pin "1") (pinfunction "1_1") (pintype "passive"))
    )
    (net (code "71") (name "unconnected-(U3-BP-Pad4)") (class "Default")
      (node (ref "U3") (pin "4") (pinfunction "BP_4") (pintype "input"))
    )
    (net (code "72") (name "unconnected-(U4-CBUS0-Pad18)") (class "Default")
      (node (ref "U4") (pin "18") (pinfunction "CBUS0_18") (pintype "bidirectional"))
    )
    (net (code "73") (name "unconnected-(U4-CBUS1-Pad17)") (class "Default")
      (node (ref "U4") (pin "17") (pinfunction "CBUS1_17") (pintype "bidirectional"))
    )
    (net (code "74") (name "unconnected-(U4-CBUS2-Pad10)") (class "Default")
      (node (ref "U4") (pin "10") (pinfunction "CBUS2_10") (pintype "bidirectional"))
    )
    (net (code "75") (name "unconnected-(U4-CBUS3-Pad19)") (class "Default")
      (node (ref "U4") (pin "19") (pinfunction "CBUS3_19") (pintype "bidirectional"))
    )
    (net (code "76") (name "unconnected-(U4-~{CTS}-Pad9)") (class "Default")
      (node (ref "U4") (pin "9") (pinfunction "~{CTS}_9") (pintype "bidirectional"))
    )
    (net (code "77") (name "unconnected-(U4-~{DCD}-Pad8)") (class "Default")
      (node (ref "U4") (pin "8") (pinfunction "~{DCD}_8") (pintype "bidirectional"))
    )
    (net (code "78") (name "unconnected-(U4-~{DSR}-Pad7)") (class "Default")
      (node (ref "U4") (pin "7") (pinfunction "~{DSR}_7") (pintype "bidirectional"))
    )
    (net (code "79") (name "unconnected-(U4-~{RI}-Pad5)") (class "Default")
      (node (ref "U4") (pin "5") (pinfunction "~{RI}_5") (pintype "bidirectional"))
    )
  )
)
